# ESP32-S3-WROOM-1-N8.net
KiCad netlist of a schematic drawn in EAGLE
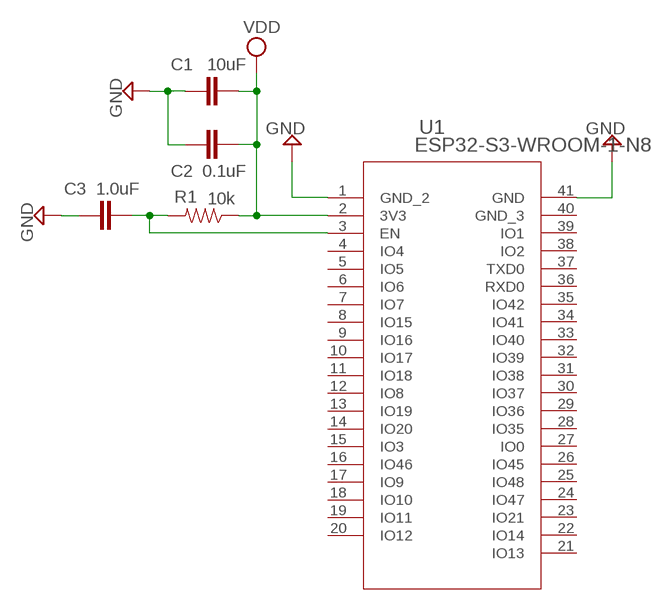
[diagram p0: schematic, sheet 1]

(export (version "E")
  (design (tool "Eeschema 10.0.6"))
  (components
    (comp (ref "C1")
      (value "10uF")
      (footprint "eagle-import:0402-TIGHT")
      (libsource (lib "eagle-import") (part "10UF-0402T-6.3V-20%"))
    )
    (comp (ref "C2")
      (value "0.1uF")
      (footprint "eagle-import:0402-TIGHT")
      (libsource (lib "eagle-import") (part "0.1UF-0402T-6.3V-10%-X7R"))
    )
    (comp (ref "C3")
      (value "1.0uF")
      (footprint "eagle-import:0402-TIGHT")
      (libsource (lib "eagle-import") (part "1.0UF-0402T-16V-10%"))
    )
    (comp (ref "R1")
      (value "10k")
      (footprint "eagle-import:0402")
      (libsource (lib "eagle-import") (part "10KOHM-0402-1/16W-1%"))
    )
    (comp (ref "U1")
      (value "ESP32-S3-WROOM-1-N8")
      (footprint "eagle-import:ESP32-S3-WROOM-1-N8_EXP")
      (fields (field (name "COPYRIGHT") "Copyright (C) 2022 Ultra Librarian. All rights reserved."))
      (libsource (lib "eagle-import") (part "ESP32-S3-WROOM-1-N8"))
    )
  )
  (nets
    (net (code "1") (name "GND") (class "Default")
      (node (ref "C1") (pin "1") (pinfunction "1_1") (pintype "passive"))
      (node (ref "C2") (pin "1") (pinfunction "1_1") (pintype "passive"))
      (node (ref "C3") (pin "1") (pinfunction "1_1") (pintype "passive"))
      (node (ref "U1") (pin "1") (pinfunction "GND_2_1") (pintype "passive"))
      (node (ref "U1") (pin "41") (pinfunction "GND_41") (pintype "passive"))
    )
    (net (code "2") (name "Net-(U1-EN)") (class "Default")
      (node (ref "C3") (pin "2") (pinfunction "2_2") (pintype "passive"))
      (node (ref "R1") (pin "2") (pinfunction "2_2") (pintype "passive"))
      (node (ref "U1") (pin "3") (pinfunction "EN_3") (pintype "input"))
    )
    (net (code "3") (name "VDD") (class "Default")
      (node (ref "C1") (pin "2") (pinfunction "2_2") (pintype "passive"))
      (node (ref "C2") (pin "2") (pinfunction "2_2") (pintype "passive"))
      (node (ref "R1") (pin "1") (pinfunction "1_1") (pintype "passive"))
      (node (ref "U1") (pin "2") (pinfunction "3V3_2") (pintype "power_in"))
    )
    (net (code "4") (name "unconnected-(U1-GND_3-Pad40)") (class "Default")
      (node (ref "U1") (pin "40") (pinfunction "GND_3_40") (pintype "passive"))
    )
    (net (code "5") (name "unconnected-(U1-IO0-Pad27)") (class "Default")
      (node (ref "U1") (pin "27") (pinfunction "IO0_27") (pintype "bidirectional"))
    )
    (net (code "6") (name "unconnected-(U1-IO1-Pad39)") (class "Default")
      (node (ref "U1") (pin "39") (pinfunction "IO1_39") (pintype "bidirectional"))
    )
    (net (code "7") (name "unconnected-(U1-IO2-Pad38)") (class "Default")
      (node (ref "U1") (pin "38") (pinfunction "IO2_38") (pintype "bidirectional"))
    )
    (net (code "8") (name "unconnected-(U1-IO3-Pad15)") (class "Default")
      (node (ref "U1") (pin "15") (pinfunction "IO3_15") (pintype "bidirectional"))
    )
    (net (code "9") (name "unconnected-(U1-IO4-Pad4)") (class "Default")
      (node (ref "U1") (pin "4") (pinfunction "IO4_4") (pintype "bidirectional"))
    )
    (net (code "10") (name "unconnected-(U1-IO5-Pad5)") (class "Default")
      (node (ref "U1") (pin "5") (pinfunction "IO5_5") (pintype "bidirectional"))
    )
    (net (code "11") (name "unconnected-(U1-IO6-Pad6)") (class "Default")
      (node (ref "U1") (pin "6") (pinfunction "IO6_6") (pintype "bidirectional"))
    )
    (net (code "12") (name "unconnected-(U1-IO7-Pad7)") (class "Default")
      (node (ref "U1") (pin "7") (pinfunction "IO7_7") (pintype "bidirectional"))
    )
    (net (code "13") (name "unconnected-(U1-IO8-Pad12)") (class "Default")
      (node (ref "U1") (pin "12") (pinfunction "IO8_12") (pintype "bidirectional"))
    )
    (net (code "14") (name "unconnected-(U1-IO9-Pad17)") (class "Default")
      (node (ref "U1") (pin "17") (pinfunction "IO9_17") (pintype "bidirectional"))
    )
    (net (code "15") (name "unconnected-(U1-IO10-Pad18)") (class "Default")
      (node (ref "U1") (pin "18") (pinfunction "IO10_18") (pintype "bidirectional"))
    )
    (net (code "16") (name "unconnected-(U1-IO11-Pad19)") (class "Default")
      (node (ref "U1") (pin "19") (pinfunction "IO11_19") (pintype "bidirectional"))
    )
    (net (code "17") (name "unconnected-(U1-IO12-Pad20)") (class "Default")
      (node (ref "U1") (pin "20") (pinfunction "IO12_20") (pintype "bidirectional"))
    )
    (net (code "18") (name "unconnected-(U1-IO13-Pad21)") (class "Default")
      (node (ref "U1") (pin "21") (pinfunction "IO13_21") (pintype "bidirectional"))
    )
    (net (code "19") (name "unconnected-(U1-IO14-Pad22)") (class "Default")
      (node (ref "U1") (pin "22") (pinfunction "IO14_22") (pintype "bidirectional"))
    )
    (net (code "20") (name "unconnected-(U1-IO15-Pad8)") (class "Default")
      (node (ref "U1") (pin "8") (pinfunction "IO15_8") (pintype "bidirectional"))
    )
    (net (code "21") (name "unconnected-(U1-IO16-Pad9)") (class "Default")
      (node (ref "U1") (pin "9") (pinfunction "IO16_9") (pintype "bidirectional"))
    )
    (net (code "22") (name "unconnected-(U1-IO17-Pad10)") (class "Default")
      (node (ref "U1") (pin "10") (pinfunction "IO17_10") (pintype "bidirectional"))
    )
    (net (code "23") (name "unconnected-(U1-IO18-Pad11)") (class "Default")
      (node (ref "U1") (pin "11") (pinfunction "IO18_11") (pintype "bidirectional"))
    )
    (net (code "24") (name "unconnected-(U1-IO19-Pad13)") (class "Default")
      (node (ref "U1") (pin "13") (pinfunction "IO19_13") (pintype "bidirectional"))
    )
    (net (code "25") (name "unconnected-(U1-IO20-Pad14)") (class "Default")
      (node (ref "U1") (pin "14") (pinfunction "IO20_14") (pintype "bidirectional"))
    )
    (net (code "26") (name "unconnected-(U1-IO21-Pad23)") (class "Default")
      (node (ref "U1") (pin "23") (pinfunction "IO21_23") (pintype "bidirectional"))
    )
    (net (code "27") (name "unconnected-(U1-IO35-Pad28)") (class "Default")
      (node (ref "U1") (pin "28") (pinfunction "IO35_28") (pintype "bidirectional"))
    )
    (net (code "28") (name "unconnected-(U1-IO36-Pad29)") (class "Default")
      (node (ref "U1") (pin "29") (pinfunction "IO36_29") (pintype "bidirectional"))
    )
    (net (code "29") (name "unconnected-(U1-IO37-Pad30)") (class "Default")
      (node (ref "U1") (pin "30") (pinfunction "IO37_30") (pintype "bidirectional"))
    )
    (net (code "30") (name "unconnected-(U1-IO38-Pad31)") (class "Default")
      (node (ref "U1") (pin "31") (pinfunction "IO38_31") (pintype "bidirectional"))
    )
    (net (code "31") (name "unconnected-(U1-IO39-Pad32)") (class "Default")
      (node (ref "U1") (pin "32") (pinfunction "IO39_32") (pintype "bidirectional"))
    )
    (net (code "32") (name "unconnected-(U1-IO40-Pad33)") (class "Default")
      (node (ref "U1") (pin "33") (pinfunction "IO40_33") (pintype "bidirectional"))
    )
    (net (code "33") (name "unconnected-(U1-IO41-Pad34)") (class "Default")
      (node (ref "U1") (pin "34") (pinfunction "IO41_34") (pintype "bidirectional"))
    )
    (net (code "34") (name "unconnected-(U1-IO42-Pad35)") (class "Default")
      (node (ref "U1") (pin "35") (pinfunction "IO42_35") (pintype "bidirectional"))
    )
    (net (code "35") (name "unconnected-(U1-IO45-Pad26)") (class "Default")
      (node (ref "U1") (pin "26") (pinfunction "IO45_26") (pintype "bidirectional"))
    )
    (net (code "36") (name "unconnected-(U1-IO46-Pad16)") (class "Default")
      (node (ref "U1") (pin "16") (pinfunction "IO46_16") (pintype "bidirectional"))
    )
    (net (code "37") (name "unconnected-(U1-IO47-Pad24)") (class "Default")
      (node (ref "U1") (pin "24") (pinfunction "IO47_24") (pintype "bidirectional"))
    )
    (net (code "38") (name "unconnected-(U1-IO48-Pad25)") (class "Default")
      (node (ref "U1") (pin "25") (pinfunction "IO48_25") (pintype "bidirectional"))
    )
    (net (code "39") (name "unconnected-(U1-RXD0-Pad36)") (class "Default")
      (node (ref "U1") (pin "36") (pinfunction "RXD0_36") (pintype "bidirectional"))
    )
    (net (code "40") (name "unconnected-(U1-TXD0-Pad37)") (class "Default")
      (node (ref "U1") (pin "37") (pinfunction "TXD0_37") (pintype "bidirectional"))
    )
  )
)
